# power.net
KiCad netlist of a schematic drawn in EAGLE
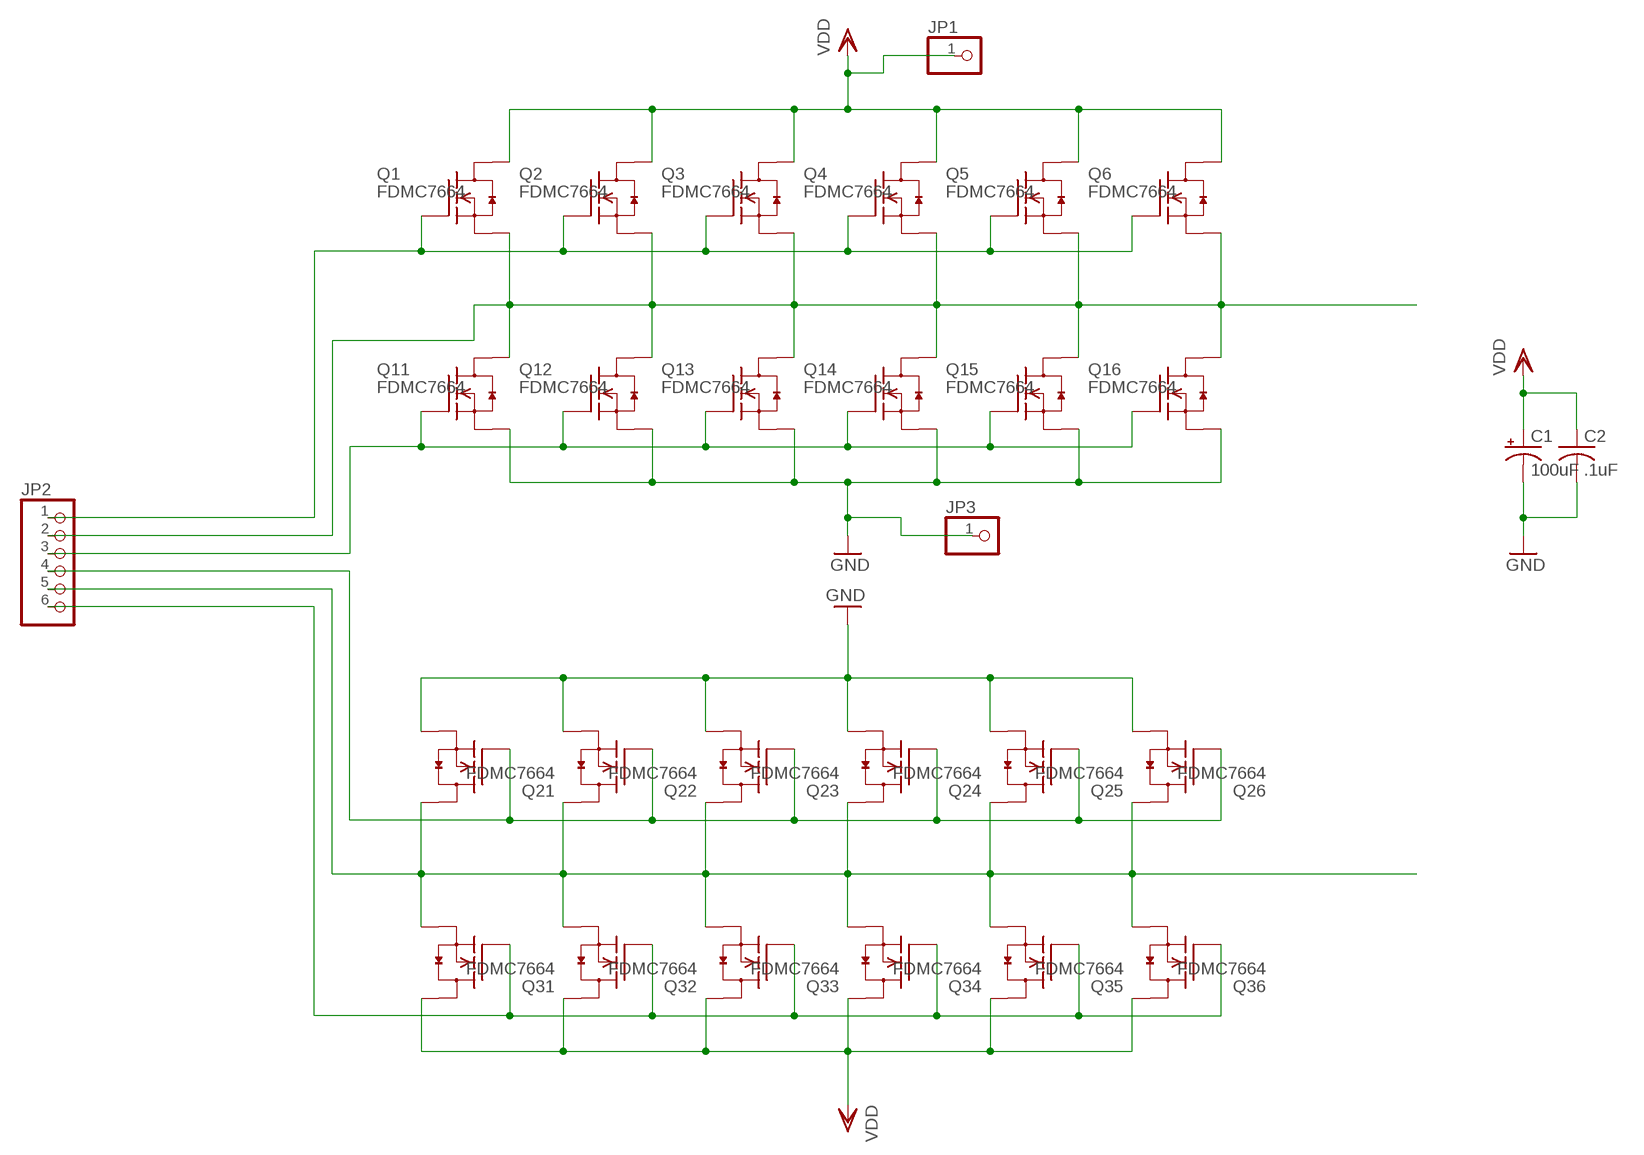
[diagram p0: schematic, sheet 1]

(export (version "E")
  (design (tool "Eeschema 10.0.6"))
  (components
    (comp (ref "C1")
      (value "100uF")
      (footprint "eagle-import:140CLH-0810")
      (libsource (lib "eagle-import") (part "CPOL-US140CLH-0810"))
    )
    (comp (ref "C2")
      (value ".1uF")
      (footprint "eagle-import:C0603")
      (libsource (lib "eagle-import") (part "C-USC0603"))
    )
    (comp (ref "JP1")
      (value "PINHD-1X1")
      (footprint "eagle-import:1X01")
      (libsource (lib "eagle-import") (part "PINHD-1X1"))
    )
    (comp (ref "JP2")
      (value "PINHD-1X6")
      (footprint "eagle-import:1X06")
      (libsource (lib "eagle-import") (part "PINHD-1X6"))
    )
    (comp (ref "JP3")
      (value "PINHD-1X1")
      (footprint "eagle-import:1X01")
      (libsource (lib "eagle-import") (part "PINHD-1X1"))
    )
    (comp (ref "Q1")
      (value "FDMC7664")
      (footprint "eagle-import:MLP33")
      (libsource (lib "eagle-import") (part "FDMC7664"))
    )
    (comp (ref "Q2")
      (value "FDMC7664")
      (footprint "eagle-import:MLP33")
      (libsource (lib "eagle-import") (part "FDMC7664"))
    )
    (comp (ref "Q3")
      (value "FDMC7664")
      (footprint "eagle-import:MLP33")
      (libsource (lib "eagle-import") (part "FDMC7664"))
    )
    (comp (ref "Q4")
      (value "FDMC7664")
      (footprint "eagle-import:MLP33")
      (libsource (lib "eagle-import") (part "FDMC7664"))
    )
    (comp (ref "Q5")
      (value "FDMC7664")
      (footprint "eagle-import:MLP33")
      (libsource (lib "eagle-import") (part "FDMC7664"))
    )
    (comp (ref "Q6")
      (value "FDMC7664")
      (footprint "eagle-import:MLP33")
      (libsource (lib "eagle-import") (part "FDMC7664"))
    )
    (comp (ref "Q11")
      (value "FDMC7664")
      (footprint "eagle-import:MLP33")
      (libsource (lib "eagle-import") (part "FDMC7664"))
    )
    (comp (ref "Q12")
      (value "FDMC7664")
      (footprint "eagle-import:MLP33")
      (libsource (lib "eagle-import") (part "FDMC7664"))
    )
    (comp (ref "Q13")
      (value "FDMC7664")
      (footprint "eagle-import:MLP33")
      (libsource (lib "eagle-import") (part "FDMC7664"))
    )
    (comp (ref "Q14")
      (value "FDMC7664")
      (footprint "eagle-import:MLP33")
      (libsource (lib "eagle-import") (part "FDMC7664"))
    )
    (comp (ref "Q15")
      (value "FDMC7664")
      (footprint "eagle-import:MLP33")
      (libsource (lib "eagle-import") (part "FDMC7664"))
    )
    (comp (ref "Q16")
      (value "FDMC7664")
      (footprint "eagle-import:MLP33")
      (libsource (lib "eagle-import") (part "FDMC7664"))
    )
    (comp (ref "Q21")
      (value "FDMC7664")
      (footprint "eagle-import:MLP33")
      (libsource (lib "eagle-import") (part "FDMC7664"))
    )
    (comp (ref "Q22")
      (value "FDMC7664")
      (footprint "eagle-import:MLP33")
      (libsource (lib "eagle-import") (part "FDMC7664"))
    )
    (comp (ref "Q23")
      (value "FDMC7664")
      (footprint "eagle-import:MLP33")
      (libsource (lib "eagle-import") (part "FDMC7664"))
    )
    (comp (ref "Q24")
      (value "FDMC7664")
      (footprint "eagle-import:MLP33")
      (libsource (lib "eagle-import") (part "FDMC7664"))
    )
    (comp (ref "Q25")
      (value "FDMC7664")
      (footprint "eagle-import:MLP33")
      (libsource (lib "eagle-import") (part "FDMC7664"))
    )
    (comp (ref "Q26")
      (value "FDMC7664")
      (footprint "eagle-import:MLP33")
      (libsource (lib "eagle-import") (part "FDMC7664"))
    )
    (comp (ref "Q31")
      (value "FDMC7664")
      (footprint "eagle-import:MLP33")
      (libsource (lib "eagle-import") (part "FDMC7664"))
    )
    (comp (ref "Q32")
      (value "FDMC7664")
      (footprint "eagle-import:MLP33")
      (libsource (lib "eagle-import") (part "FDMC7664"))
    )
    (comp (ref "Q33")
      (value "FDMC7664")
      (footprint "eagle-import:MLP33")
      (libsource (lib "eagle-import") (part "FDMC7664"))
    )
    (comp (ref "Q34")
      (value "FDMC7664")
      (footprint "eagle-import:MLP33")
      (libsource (lib "eagle-import") (part "FDMC7664"))
    )
    (comp (ref "Q35")
      (value "FDMC7664")
      (footprint "eagle-import:MLP33")
      (libsource (lib "eagle-import") (part "FDMC7664"))
    )
    (comp (ref "Q36")
      (value "FDMC7664")
      (footprint "eagle-import:MLP33")
      (libsource (lib "eagle-import") (part "FDMC7664"))
    )
  )
  (nets
    (net (code "1") (name "GND") (class "Default")
      (node (ref "C1") (pin "-") (pinfunction "-_-") (pintype "passive"))
      (node (ref "C2") (pin "2") (pinfunction "2_2") (pintype "passive"))
      (node (ref "JP3") (pin "1") (pinfunction "1_1") (pintype "passive"))
      (node (ref "Q11") (pin "123S") (pinfunction "S_123S") (pintype "passive"))
      (node (ref "Q12") (pin "123S") (pinfunction "S_123S") (pintype "passive"))
      (node (ref "Q13") (pin "123S") (pinfunction "S_123S") (pintype "passive"))
      (node (ref "Q14") (pin "123S") (pinfunction "S_123S") (pintype "passive"))
      (node (ref "Q15") (pin "123S") (pinfunction "S_123S") (pintype "passive"))
      (node (ref "Q16") (pin "123S") (pinfunction "S_123S") (pintype "passive"))
      (node (ref "Q21") (pin "123S") (pinfunction "S_123S") (pintype "passive"))
      (node (ref "Q22") (pin "123S") (pinfunction "S_123S") (pintype "passive"))
      (node (ref "Q23") (pin "123S") (pinfunction "S_123S") (pintype "passive"))
      (node (ref "Q24") (pin "123S") (pinfunction "S_123S") (pintype "passive"))
      (node (ref "Q25") (pin "123S") (pinfunction "S_123S") (pintype "passive"))
      (node (ref "Q26") (pin "123S") (pinfunction "S_123S") (pintype "passive"))
    )
    (net (code "2") (name "Net-(Q1-G)") (class "Default")
      (node (ref "JP2") (pin "1") (pinfunction "1_1") (pintype "passive"))
      (node (ref "Q1") (pin "4G") (pinfunction "G_4G") (pintype "passive"))
      (node (ref "Q2") (pin "4G") (pinfunction "G_4G") (pintype "passive"))
      (node (ref "Q3") (pin "4G") (pinfunction "G_4G") (pintype "passive"))
      (node (ref "Q4") (pin "4G") (pinfunction "G_4G") (pintype "passive"))
      (node (ref "Q5") (pin "4G") (pinfunction "G_4G") (pintype "passive"))
      (node (ref "Q6") (pin "4G") (pinfunction "G_4G") (pintype "passive"))
    )
    (net (code "3") (name "Net-(Q1-S)") (class "Default")
      (node (ref "JP2") (pin "2") (pinfunction "2_2") (pintype "passive"))
      (node (ref "Q1") (pin "123S") (pinfunction "S_123S") (pintype "passive"))
      (node (ref "Q11") (pin "5678D") (pinfunction "D_5678D") (pintype "passive"))
      (node (ref "Q12") (pin "5678D") (pinfunction "D_5678D") (pintype "passive"))
      (node (ref "Q13") (pin "5678D") (pinfunction "D_5678D") (pintype "passive"))
      (node (ref "Q14") (pin "5678D") (pinfunction "D_5678D") (pintype "passive"))
      (node (ref "Q15") (pin "5678D") (pinfunction "D_5678D") (pintype "passive"))
      (node (ref "Q16") (pin "5678D") (pinfunction "D_5678D") (pintype "passive"))
      (node (ref "Q2") (pin "123S") (pinfunction "S_123S") (pintype "passive"))
      (node (ref "Q3") (pin "123S") (pinfunction "S_123S") (pintype "passive"))
      (node (ref "Q4") (pin "123S") (pinfunction "S_123S") (pintype "passive"))
      (node (ref "Q5") (pin "123S") (pinfunction "S_123S") (pintype "passive"))
      (node (ref "Q6") (pin "123S") (pinfunction "S_123S") (pintype "passive"))
    )
    (net (code "4") (name "Net-(Q11-G)") (class "Default")
      (node (ref "JP2") (pin "3") (pinfunction "3_3") (pintype "passive"))
      (node (ref "Q11") (pin "4G") (pinfunction "G_4G") (pintype "passive"))
      (node (ref "Q12") (pin "4G") (pinfunction "G_4G") (pintype "passive"))
      (node (ref "Q13") (pin "4G") (pinfunction "G_4G") (pintype "passive"))
      (node (ref "Q14") (pin "4G") (pinfunction "G_4G") (pintype "passive"))
      (node (ref "Q15") (pin "4G") (pinfunction "G_4G") (pintype "passive"))
      (node (ref "Q16") (pin "4G") (pinfunction "G_4G") (pintype "passive"))
    )
    (net (code "5") (name "Net-(Q21-D)") (class "Default")
      (node (ref "JP2") (pin "5") (pinfunction "5_5") (pintype "passive"))
      (node (ref "Q21") (pin "5678D") (pinfunction "D_5678D") (pintype "passive"))
      (node (ref "Q22") (pin "5678D") (pinfunction "D_5678D") (pintype "passive"))
      (node (ref "Q23") (pin "5678D") (pinfunction "D_5678D") (pintype "passive"))
      (node (ref "Q24") (pin "5678D") (pinfunction "D_5678D") (pintype "passive"))
      (node (ref "Q25") (pin "5678D") (pinfunction "D_5678D") (pintype "passive"))
      (node (ref "Q26") (pin "5678D") (pinfunction "D_5678D") (pintype "passive"))
      (node (ref "Q31") (pin "123S") (pinfunction "S_123S") (pintype "passive"))
      (node (ref "Q32") (pin "123S") (pinfunction "S_123S") (pintype "passive"))
      (node (ref "Q33") (pin "123S") (pinfunction "S_123S") (pintype "passive"))
      (node (ref "Q34") (pin "123S") (pinfunction "S_123S") (pintype "passive"))
      (node (ref "Q35") (pin "123S") (pinfunction "S_123S") (pintype "passive"))
      (node (ref "Q36") (pin "123S") (pinfunction "S_123S") (pintype "passive"))
    )
    (net (code "6") (name "Net-(Q21-G)") (class "Default")
      (node (ref "JP2") (pin "4") (pinfunction "4_4") (pintype "passive"))
      (node (ref "Q21") (pin "4G") (pinfunction "G_4G") (pintype "passive"))
      (node (ref "Q22") (pin "4G") (pinfunction "G_4G") (pintype "passive"))
      (node (ref "Q23") (pin "4G") (pinfunction "G_4G") (pintype "passive"))
      (node (ref "Q24") (pin "4G") (pinfunction "G_4G") (pintype "passive"))
      (node (ref "Q25") (pin "4G") (pinfunction "G_4G") (pintype "passive"))
      (node (ref "Q26") (pin "4G") (pinfunction "G_4G") (pintype "passive"))
    )
    (net (code "7") (name "Net-(Q31-G)") (class "Default")
      (node (ref "JP2") (pin "6") (pinfunction "6_6") (pintype "passive"))
      (node (ref "Q31") (pin "4G") (pinfunction "G_4G") (pintype "passive"))
      (node (ref "Q32") (pin "4G") (pinfunction "G_4G") (pintype "passive"))
      (node (ref "Q33") (pin "4G") (pinfunction "G_4G") (pintype "passive"))
      (node (ref "Q34") (pin "4G") (pinfunction "G_4G") (pintype "passive"))
      (node (ref "Q35") (pin "4G") (pinfunction "G_4G") (pintype "passive"))
      (node (ref "Q36") (pin "4G") (pinfunction "G_4G") (pintype "passive"))
    )
    (net (code "8") (name "VDD") (class "Default")
      (node (ref "C1") (pin "+") (pinfunction "+_+") (pintype "passive"))
      (node (ref "C2") (pin "1") (pinfunction "1_1") (pintype "passive"))
      (node (ref "JP1") (pin "1") (pinfunction "1_1") (pintype "passive"))
      (node (ref "Q1") (pin "5678D") (pinfunction "D_5678D") (pintype "passive"))
      (node (ref "Q2") (pin "5678D") (pinfunction "D_5678D") (pintype "passive"))
      (node (ref "Q3") (pin "5678D") (pinfunction "D_5678D") (pintype "passive"))
      (node (ref "Q31") (pin "5678D") (pinfunction "D_5678D") (pintype "passive"))
      (node (ref "Q32") (pin "5678D") (pinfunction "D_5678D") (pintype "passive"))
      (node (ref "Q33") (pin "5678D") (pinfunction "D_5678D") (pintype "passive"))
      (node (ref "Q34") (pin "5678D") (pinfunction "D_5678D") (pintype "passive"))
      (node (ref "Q35") (pin "5678D") (pinfunction "D_5678D") (pintype "passive"))
      (node (ref "Q36") (pin "5678D") (pinfunction "D_5678D") (pintype "passive"))
      (node (ref "Q4") (pin "5678D") (pinfunction "D_5678D") (pintype "passive"))
      (node (ref "Q5") (pin "5678D") (pinfunction "D_5678D") (pintype "passive"))
      (node (ref "Q6") (pin "5678D") (pinfunction "D_5678D") (pintype "passive"))
    )
  )
)
